# Sheet1.net
KiCad netlist of a schematic drawn in Altium Designer
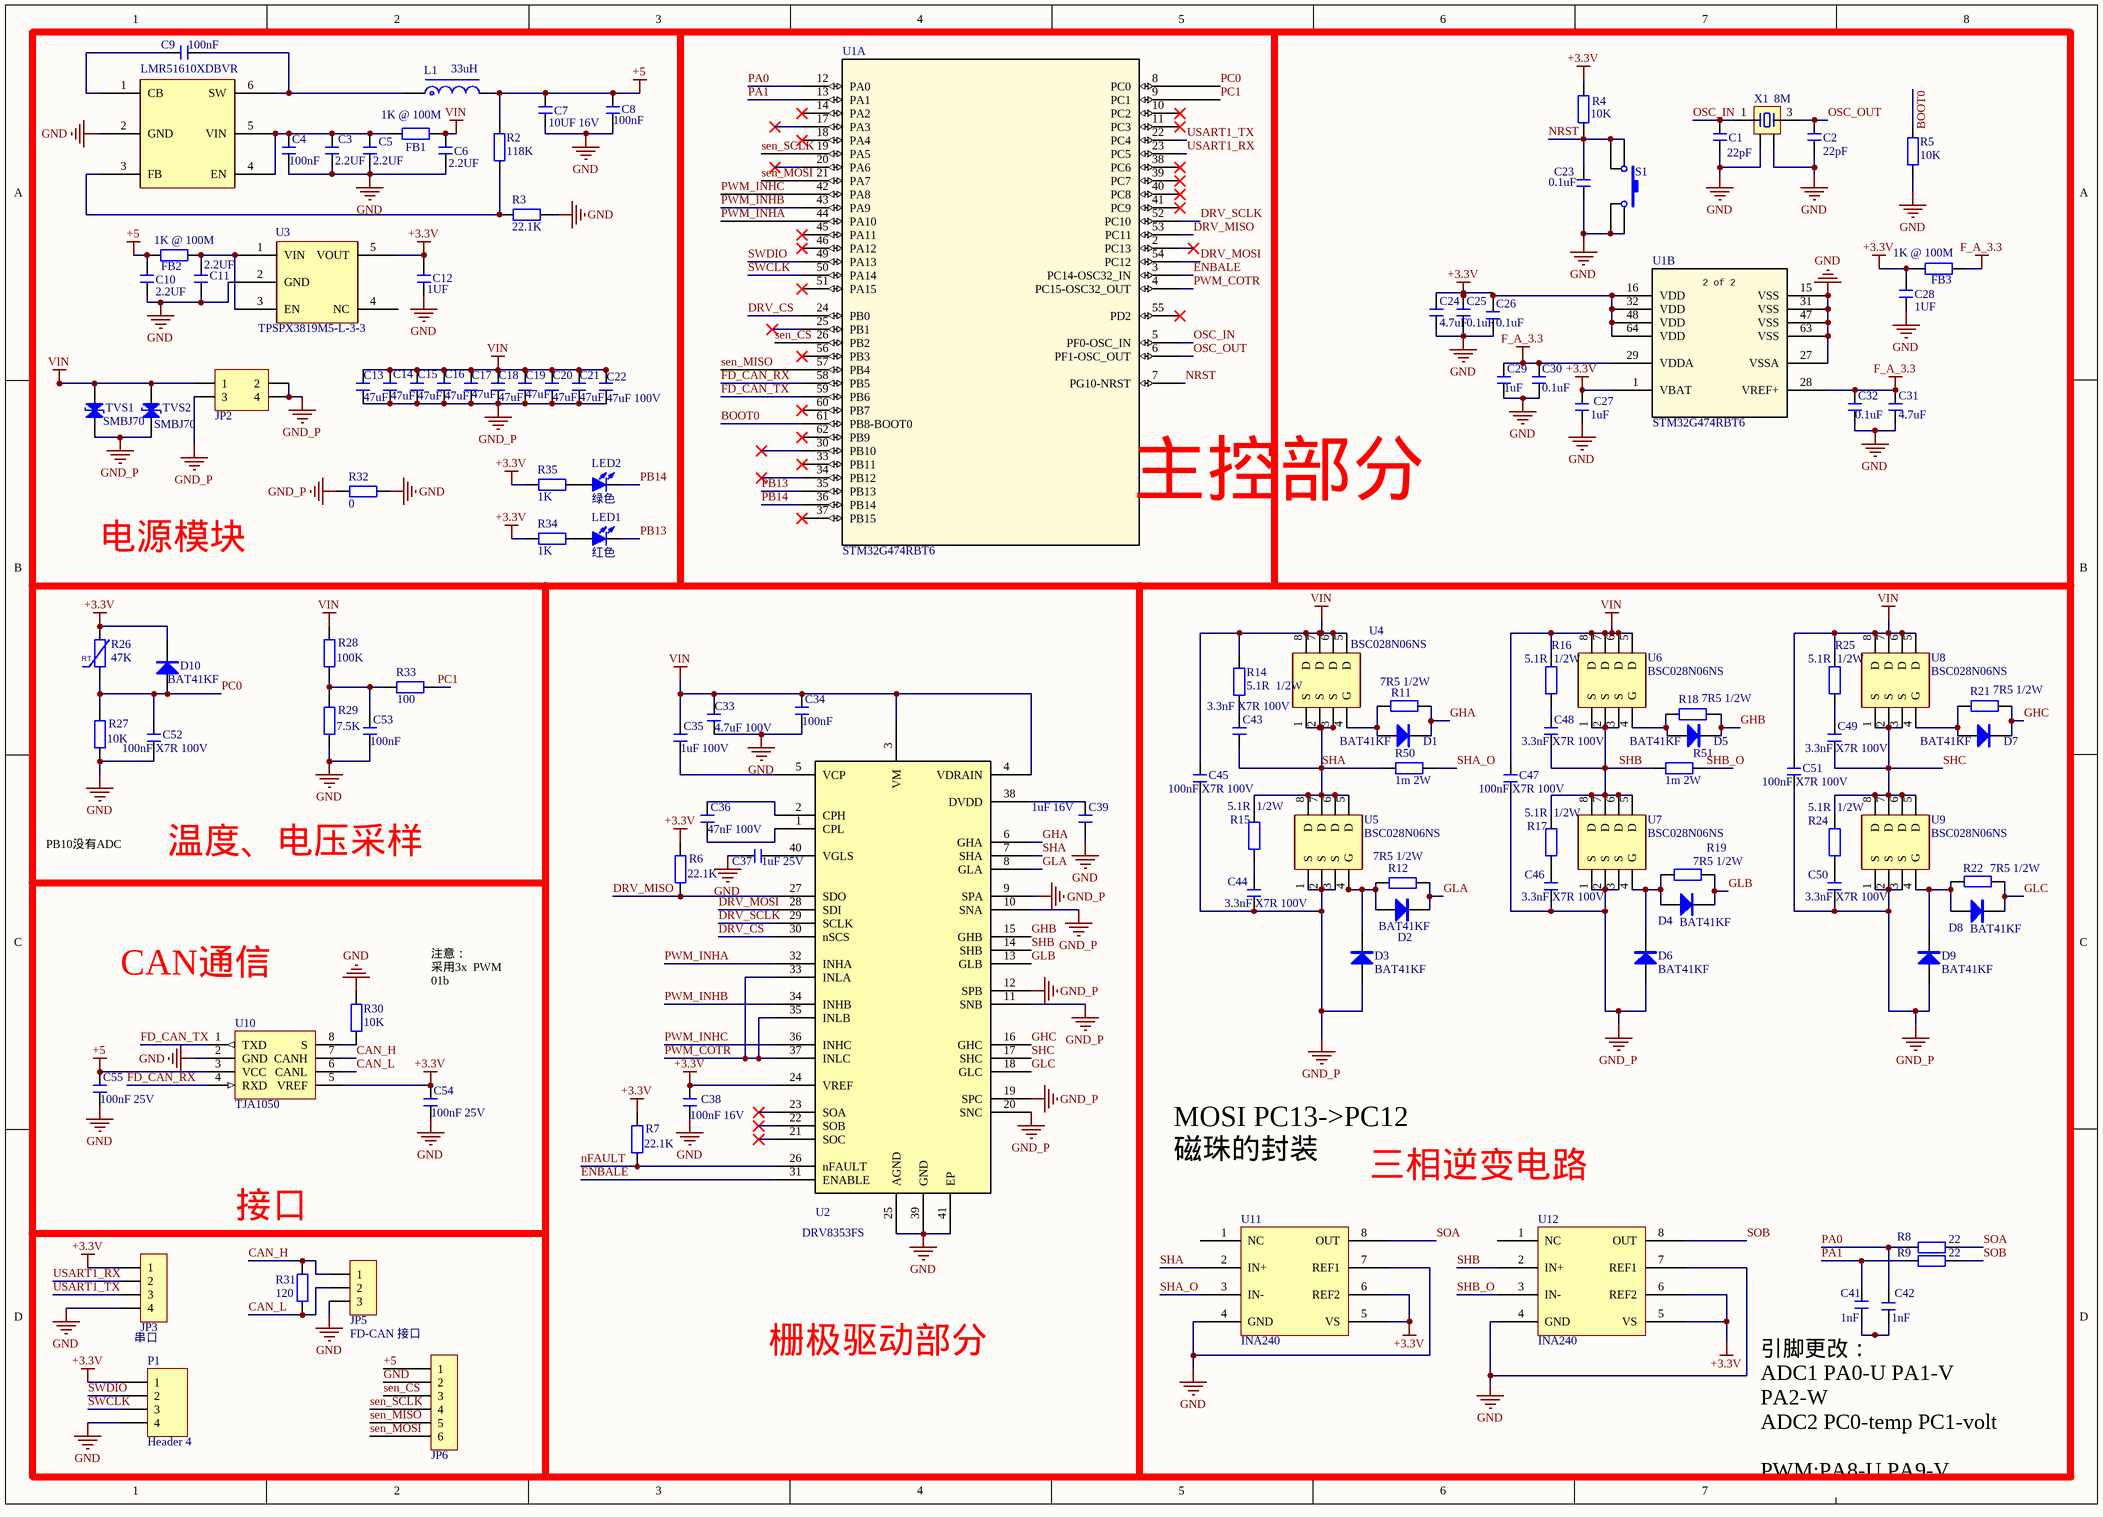
[diagram p0: Sheet1.SchDoc]

(export (version "E")
  (design (tool "Eeschema 10.0.6"))
  (components
    (comp (ref "C1")
      (value "22pF")
      (footprint "C0402_L")
      (description "贴片电容")
      (libsource (lib "0.1 - 电阻-电容-电感") (part "C"))
    )
    (comp (ref "C2")
      (value "22pF")
      (footprint "C0402_L")
      (description "贴片电容")
      (libsource (lib "0.1 - 电阻-电容-电感") (part "C"))
    )
    (comp (ref "C3")
      (value "2.2UF")
      (footprint "C0603_L")
      (description "贴片电容")
      (libsource (lib "0.1 - 电阻-电容-电感") (part "C"))
    )
    (comp (ref "C4")
      (value "100nF")
      (footprint "C0603_L")
      (description "贴片电容")
      (libsource (lib "0.1 - 电阻-电容-电感") (part "C"))
    )
    (comp (ref "C5")
      (value "2.2UF")
      (footprint "C0603_L")
      (description "贴片电容")
      (libsource (lib "0.1 - 电阻-电容-电感") (part "C"))
    )
    (comp (ref "C6")
      (value "2.2UF")
      (footprint "C0603_L")
      (description "贴片电容")
      (libsource (lib "0.1 - 电阻-电容-电感") (part "C"))
    )
    (comp (ref "C7")
      (value "10UF 16V")
      (footprint "C0402_L")
      (description "贴片电容")
      (libsource (lib "0.1 - 电阻-电容-电感") (part "C"))
    )
    (comp (ref "C8")
      (value "100nF")
      (footprint "C0402_L")
      (description "贴片电容")
      (libsource (lib "0.1 - 电阻-电容-电感") (part "C"))
    )
    (comp (ref "C9")
      (value "100nF")
      (footprint "C0603_L")
      (description "贴片电容")
      (libsource (lib "0.1 - 电阻-电容-电感") (part "C"))
    )
    (comp (ref "C10")
      (value "2.2UF")
      (footprint "C0402_L")
      (description "贴片电容")
      (libsource (lib "0.1 - 电阻-电容-电感") (part "C"))
    )
    (comp (ref "C11")
      (value "2.2UF")
      (footprint "C0402_L")
      (description "贴片电容")
      (libsource (lib "0.1 - 电阻-电容-电感") (part "C"))
    )
    (comp (ref "C12")
      (value "1UF")
      (footprint "C0402_L")
      (description "贴片电容")
      (libsource (lib "0.1 - 电阻-电容-电感") (part "C"))
    )
    (comp (ref "C13")
      (value "47uF")
      (footprint "C1206_L")
      (description "贴片电容")
      (libsource (lib "0.1 - 电阻-电容-电感") (part "C"))
    )
    (comp (ref "C14")
      (value "47uF")
      (footprint "C1206_L")
      (description "贴片电容")
      (libsource (lib "0.1 - 电阻-电容-电感") (part "C"))
    )
    (comp (ref "C15")
      (value "47uF")
      (footprint "C1206_L")
      (description "贴片电容")
      (libsource (lib "0.1 - 电阻-电容-电感") (part "C"))
    )
    (comp (ref "C16")
      (value "47uF")
      (footprint "C1206_L")
      (description "贴片电容")
      (libsource (lib "0.1 - 电阻-电容-电感") (part "C"))
    )
    (comp (ref "C17")
      (value "47uF")
      (footprint "C1206_L")
      (description "贴片电容")
      (libsource (lib "0.1 - 电阻-电容-电感") (part "C"))
    )
    (comp (ref "C18")
      (value "47uF")
      (footprint "C1206_L")
      (description "贴片电容")
      (libsource (lib "0.1 - 电阻-电容-电感") (part "C"))
    )
    (comp (ref "C19")
      (value "47uF")
      (footprint "C1206_L")
      (description "贴片电容")
      (libsource (lib "0.1 - 电阻-电容-电感") (part "C"))
    )
    (comp (ref "C20")
      (value "47uF")
      (footprint "C1206_L")
      (description "贴片电容")
      (libsource (lib "0.1 - 电阻-电容-电感") (part "C"))
    )
    (comp (ref "C21")
      (value "47uF")
      (footprint "C1206_L")
      (description "贴片电容")
      (libsource (lib "0.1 - 电阻-电容-电感") (part "C"))
    )
    (comp (ref "C22")
      (value "47uF 100V")
      (footprint "C1206_L")
      (description "贴片电容")
      (libsource (lib "0.1 - 电阻-电容-电感") (part "C"))
    )
    (comp (ref "C23")
      (value "0.1uF")
      (footprint "C0402_L")
      (description "贴片电容")
      (libsource (lib "0.1 - 电阻-电容-电感") (part "C"))
    )
    (comp (ref "C24")
      (value "4.7uF")
      (footprint "C0402_L")
      (description "贴片电容")
      (libsource (lib "0.1 - 电阻-电容-电感") (part "C"))
    )
    (comp (ref "C25")
      (value "0.1uF")
      (footprint "C0402_L")
      (description "贴片电容")
      (libsource (lib "0.1 - 电阻-电容-电感") (part "C"))
    )
    (comp (ref "C26")
      (value "0.1uF")
      (footprint "C0402_L")
      (description "贴片电容")
      (libsource (lib "0.1 - 电阻-电容-电感") (part "C"))
    )
    (comp (ref "C27")
      (value "1uF")
      (footprint "C0402_L")
      (description "贴片电容")
      (libsource (lib "0.1 - 电阻-电容-电感") (part "C"))
    )
    (comp (ref "C28")
      (value "1UF")
      (footprint "C0402_L")
      (description "贴片电容")
      (libsource (lib "0.1 - 电阻-电容-电感") (part "C"))
    )
    (comp (ref "C29")
      (value "1uF")
      (footprint "C0402_L")
      (description "贴片电容")
      (libsource (lib "0.1 - 电阻-电容-电感") (part "C"))
    )
    (comp (ref "C30")
      (value "0.1uF")
      (footprint "C0402_L")
      (description "贴片电容")
      (libsource (lib "0.1 - 电阻-电容-电感") (part "C"))
    )
    (comp (ref "C31")
      (value "4.7uF")
      (footprint "C0402_L")
      (description "贴片电容")
      (libsource (lib "0.1 - 电阻-电容-电感") (part "C"))
    )
    (comp (ref "C32")
      (value "0.1uF")
      (footprint "C0402_L")
      (description "贴片电容")
      (libsource (lib "0.1 - 电阻-电容-电感") (part "C"))
    )
    (comp (ref "C33")
      (value "4.7uF 100V")
      (footprint "C0603_L")
      (description "贴片电容")
      (libsource (lib "0.1 - 电阻-电容-电感") (part "C"))
    )
    (comp (ref "C34")
      (value "100nF")
      (footprint "C0603_L")
      (description "贴片电容")
      (libsource (lib "0.1 - 电阻-电容-电感") (part "C"))
    )
    (comp (ref "C35")
      (value "1uF 100V")
      (footprint "C0603_L")
      (description "贴片电容")
      (libsource (lib "0.1 - 电阻-电容-电感") (part "C"))
    )
    (comp (ref "C36")
      (value "47nF 100V")
      (footprint "C0603_L")
      (description "贴片电容")
      (libsource (lib "0.1 - 电阻-电容-电感") (part "C"))
    )
    (comp (ref "C37")
      (value "1uF 25V")
      (footprint "C0603_L")
      (description "贴片电容")
      (libsource (lib "0.1 - 电阻-电容-电感") (part "C"))
    )
    (comp (ref "C38")
      (value "100nF 16V")
      (footprint "C0402_L")
      (description "贴片电容")
      (libsource (lib "0.1 - 电阻-电容-电感") (part "C"))
    )
    (comp (ref "C39")
      (value "1uF 16V")
      (footprint "C0603_L")
      (description "贴片电容")
      (libsource (lib "0.1 - 电阻-电容-电感") (part "C"))
    )
    (comp (ref "C41")
      (value "1nF")
      (footprint "C0402_L")
      (description "贴片电容")
      (libsource (lib "0.1 - 电阻-电容-电感") (part "C"))
    )
    (comp (ref "C42")
      (value "1nF")
      (footprint "C0402_L")
      (description "贴片电容")
      (libsource (lib "0.1 - 电阻-电容-电感") (part "C"))
    )
    (comp (ref "C43")
      (value "3.3nF X7R 100V")
      (footprint "C1206_L")
      (description "贴片电容")
      (libsource (lib "0.1 - 电阻-电容-电感") (part "C"))
    )
    (comp (ref "C44")
      (value "3.3nF X7R 100V")
      (footprint "C1206_L")
      (description "贴片电容")
      (libsource (lib "0.1 - 电阻-电容-电感") (part "C"))
    )
    (comp (ref "C45")
      (value "100nF X7R 100V")
      (footprint "C0603_L")
      (description "贴片电容")
      (libsource (lib "0.1 - 电阻-电容-电感") (part "C"))
    )
    (comp (ref "C46")
      (value "3.3nF X7R 100V")
      (footprint "C1206_L")
      (description "贴片电容")
      (libsource (lib "0.1 - 电阻-电容-电感") (part "C"))
    )
    (comp (ref "C47")
      (value "100nF X7R 100V")
      (footprint "C0603_L")
      (description "贴片电容")
      (libsource (lib "0.1 - 电阻-电容-电感") (part "C"))
    )
    (comp (ref "C48")
      (value "3.3nF X7R 100V")
      (footprint "C1206_L")
      (description "贴片电容")
      (libsource (lib "0.1 - 电阻-电容-电感") (part "C"))
    )
    (comp (ref "C49")
      (value "3.3nF X7R 100V")
      (footprint "C1206_L")
      (description "贴片电容")
      (libsource (lib "0.1 - 电阻-电容-电感") (part "C"))
    )
    (comp (ref "C50")
      (value "3.3nF X7R 100V")
      (footprint "C1206_L")
      (description "贴片电容")
      (libsource (lib "0.1 - 电阻-电容-电感") (part "C"))
    )
    (comp (ref "C51")
      (value "100nF X7R 100V")
      (footprint "C0603_L")
      (description "贴片电容")
      (libsource (lib "0.1 - 电阻-电容-电感") (part "C"))
    )
    (comp (ref "C52")
      (value "100nF X7R 100V")
      (footprint "C0603_L")
      (description "贴片电容")
      (libsource (lib "0.1 - 电阻-电容-电感") (part "C"))
    )
    (comp (ref "C53")
      (value "100nF")
      (footprint "C0402_L")
      (description "贴片电容")
      (libsource (lib "0.1 - 电阻-电容-电感") (part "C"))
    )
    (comp (ref "C54")
      (value "100nF 25V")
      (footprint "C0402_L")
      (description "贴片电容")
      (libsource (lib "0.1 - 电阻-电容-电感") (part "C"))
    )
    (comp (ref "C55")
      (value "100nF 25V")
      (footprint "C0402_L")
      (description "贴片电容")
      (libsource (lib "0.1 - 电阻-电容-电感") (part "C"))
    )
    (comp (ref "D1")
      (value "BAT41KF")
      (footprint "SOD-523")
      (description "肖特基二极管")
      (fields (field (name "版权归属") "封装库来自淘宝 ID：黄晶宝石"))
      (libsource (lib "0.2 - 二极管-整流桥") (part "SR540"))
    )
    (comp (ref "D2")
      (value "BAT41KF")
      (footprint "SOD-523")
      (description "肖特基二极管")
      (fields (field (name "版权归属") "封装库来自淘宝 ID：黄晶宝石"))
      (libsource (lib "0.2 - 二极管-整流桥") (part "SR540"))
    )
    (comp (ref "D3")
      (value "BAT41KF")
      (footprint "SOD-523")
      (description "肖特基二极管")
      (fields (field (name "版权归属") "封装库来自淘宝 ID：黄晶宝石"))
      (libsource (lib "0.2 - 二极管-整流桥") (part "SR540"))
    )
    (comp (ref "D4")
      (value "BAT41KF")
      (footprint "SOD-523")
      (description "肖特基二极管")
      (fields (field (name "版权归属") "封装库来自淘宝 ID：黄晶宝石"))
      (libsource (lib "0.2 - 二极管-整流桥") (part "SR540"))
    )
    (comp (ref "D5")
      (value "BAT41KF")
      (footprint "SOD-523")
      (description "肖特基二极管")
      (fields (field (name "版权归属") "封装库来自淘宝 ID：黄晶宝石"))
      (libsource (lib "0.2 - 二极管-整流桥") (part "SR540"))
    )
    (comp (ref "D6")
      (value "BAT41KF")
      (footprint "SOD-523")
      (description "肖特基二极管")
      (fields (field (name "版权归属") "封装库来自淘宝 ID：黄晶宝石"))
      (libsource (lib "0.2 - 二极管-整流桥") (part "SR540"))
    )
    (comp (ref "D7")
      (value "BAT41KF")
      (footprint "SOD-523")
      (description "肖特基二极管")
      (fields (field (name "版权归属") "封装库来自淘宝 ID：黄晶宝石"))
      (libsource (lib "0.2 - 二极管-整流桥") (part "SR540"))
    )
    (comp (ref "D8")
      (value "BAT41KF")
      (footprint "SOD-523")
      (description "肖特基二极管")
      (fields (field (name "版权归属") "封装库来自淘宝 ID：黄晶宝石"))
      (libsource (lib "0.2 - 二极管-整流桥") (part "SR540"))
    )
    (comp (ref "D9")
      (value "BAT41KF")
      (footprint "SOD-523")
      (description "肖特基二极管")
      (fields (field (name "版权归属") "封装库来自淘宝 ID：黄晶宝石"))
      (libsource (lib "0.2 - 二极管-整流桥") (part "SR540"))
    )
    (comp (ref "D10")
      (value "BAT41KF")
      (footprint "SOD-523")
      (description "肖特基二极管")
      (fields (field (name "版权归属") "封装库来自淘宝 ID：黄晶宝石"))
      (libsource (lib "0.2 - 二极管-整流桥") (part "SR540"))
    )
    (comp (ref "FB1")
      (value "1K @ 100M")
      (footprint "R1206_L")
      (description "贴片电阻")
      (fields (field (name "版权归属") "来自淘宝 ID：黄晶宝石"))
      (libsource (lib "0.1 - 电阻-电容-电感") (part "R"))
    )
    (comp (ref "FB2")
      (value "1K @ 100M")
      (footprint "R1206_L")
      (description "贴片电阻")
      (fields (field (name "版权归属") "来自淘宝 ID：黄晶宝石"))
      (libsource (lib "0.1 - 电阻-电容-电感") (part "R"))
    )
    (comp (ref "FB3")
      (value "1K @ 100M")
      (footprint "R0805_L")
      (description "贴片电阻")
      (fields (field (name "版权归属") "来自淘宝 ID：黄晶宝石"))
      (libsource (lib "0.1 - 电阻-电容-电感") (part "R"))
    )
    (comp (ref "JP2")
      (value "Header2X2")
      (footprint "TX60PW-M20")
      (description "2*2P接插件")
      (libsource (lib "5.3 - 接插件-脚距2.0") (part "Header 2X2"))
    )
    (comp (ref "JP3")
      (value "串口")
      (footprint "MX 1.25-WI-4P")
      (description "4P接插件")
      (libsource (lib "5.0 - 接插件-脚距1.25") (part "Header 4"))
    )
    (comp (ref "JP5")
      (value "FD-CAN 接口")
      (footprint "XH2.54-WI-3P")
      (description "3P接插件")
      (fields (field (name "版权归属") "封装库来自淘宝 ID：黄晶宝石"))
      (libsource (lib "5.4 - 接插件-脚距2.54 (100mil) ") (part "Header 3"))
    )
    (comp (ref "JP6")
      (value "HDR-1X6")
      (footprint "MX 1.25-WI-6P")
      (description "6P接插件")
      (fields (field (name "版权归属") "封装库来自淘宝 ID：黄晶宝石"))
      (libsource (lib "5.0 - 接插件-脚距1.25") (part "Header 6"))
    )
    (comp (ref "L1")
      (value "33uH")
      (footprint "NR4030")
      (description "NR磁胶电感")
      (fields (field (name "版权归属") "来自淘宝 ID：黄晶宝石"))
      (libsource (lib "0.1 - 电阻-电容-电感") (part "L-NR"))
    )
    (comp (ref "LED1")
      (value "红色")
      (footprint "LED0603_R")
      (description "贴片LED")
      (fields (field (name "版权归属") "封装库来自淘宝 ID：黄晶宝石"))
      (libsource (lib "0.3 - LED发光二极管") (part "LED-SMD"))
    )
    (comp (ref "LED2")
      (value "绿色")
      (footprint "LED0603_R")
      (description "贴片LED")
      (fields (field (name "版权归属") "封装库来自淘宝 ID：黄晶宝石"))
      (libsource (lib "0.3 - LED发光二极管") (part "LED-SMD"))
    )
    (comp (ref "LMR51610XDBVR")
      (value "Component_1")
      (footprint "SOT23-6M")
      (libsource (lib "LMR51610XDBVR") (part "Component_1"))
    )
    (comp (ref "P1")
      (value "Header 4")
      (footprint "HDR1X4")
      (description "Header, 4-Pin")
      (fields (field (name "PUBLISHER") "Altium Limited"))
      (libsource (lib "Miscellaneous Connectors") (part "Header 4"))
    )
    (comp (ref "R2")
      (value "118K")
      (footprint "R0402_L")
      (description "贴片电阻")
      (fields (field (name "版权归属") "来自淘宝 ID：黄晶宝石"))
      (libsource (lib "0.1 - 电阻-电容-电感") (part "R"))
    )
    (comp (ref "R3")
      (value "22.1K")
      (footprint "R0402_L")
      (description "贴片电阻")
      (fields (field (name "版权归属") "来自淘宝 ID：黄晶宝石"))
      (libsource (lib "0.1 - 电阻-电容-电感") (part "R"))
    )
    (comp (ref "R4")
      (value "10K")
      (footprint "R0402_L")
      (description "贴片电阻")
      (fields (field (name "版权归属") "来自淘宝 ID：黄晶宝石"))
      (libsource (lib "0.1 - 电阻-电容-电感") (part "R"))
    )
    (comp (ref "R5")
      (value "10K")
      (footprint "R0402_L")
      (description "贴片电阻")
      (fields (field (name "版权归属") "来自淘宝 ID：黄晶宝石"))
      (libsource (lib "0.1 - 电阻-电容-电感") (part "R"))
    )
    (comp (ref "R6")
      (value "22.1K")
      (footprint "R0402_L")
      (description "贴片电阻")
      (fields (field (name "版权归属") "来自淘宝 ID：黄晶宝石"))
      (libsource (lib "0.1 - 电阻-电容-电感") (part "R"))
    )
    (comp (ref "R7")
      (value "22.1K")
      (footprint "R0402_L")
      (description "贴片电阻")
      (fields (field (name "版权归属") "来自淘宝 ID：黄晶宝石"))
      (libsource (lib "0.1 - 电阻-电容-电感") (part "R"))
    )
    (comp (ref "R8")
      (value "22")
      (footprint "R0402_L")
      (description "贴片电阻")
      (fields (field (name "版权归属") "来自淘宝 ID：黄晶宝石"))
      (libsource (lib "0.1 - 电阻-电容-电感") (part "R"))
    )
    (comp (ref "R9")
      (value "22")
      (footprint "R0402_L")
      (description "贴片电阻")
      (fields (field (name "版权归属") "来自淘宝 ID：黄晶宝石"))
      (libsource (lib "0.1 - 电阻-电容-电感") (part "R"))
    )
    (comp (ref "R11")
      (value "7R5 1/2W")
      (footprint "R1210_M")
      (description "贴片电阻")
      (fields (field (name "版权归属") "来自淘宝 ID：黄晶宝石"))
      (libsource (lib "0.1 - 电阻-电容-电感") (part "R"))
    )
    (comp (ref "R12")
      (value "7R5 1/2W")
      (footprint "R1210_M")
      (description "贴片电阻")
      (fields (field (name "版权归属") "来自淘宝 ID：黄晶宝石"))
      (libsource (lib "0.1 - 电阻-电容-电感") (part "R"))
    )
    (comp (ref "R14")
      (value "5.1R  1/2W")
      (footprint "R1210_L")
      (description "贴片电阻")
      (fields (field (name "版权归属") "来自淘宝 ID：黄晶宝石"))
      (libsource (lib "0.1 - 电阻-电容-电感") (part "R"))
    )
    (comp (ref "R15")
      (value "5.1R  1/2W")
      (footprint "R1210_L")
      (description "贴片电阻")
      (fields (field (name "版权归属") "来自淘宝 ID：黄晶宝石"))
      (libsource (lib "0.1 - 电阻-电容-电感") (part "R"))
    )
    (comp (ref "R16")
      (value "5.1R  1/2W")
      (footprint "R1210_L")
      (description "贴片电阻")
      (fields (field (name "版权归属") "来自淘宝 ID：黄晶宝石"))
      (libsource (lib "0.1 - 电阻-电容-电感") (part "R"))
    )
    (comp (ref "R17")
      (value "5.1R  1/2W")
      (footprint "R1210_L")
      (description "贴片电阻")
      (fields (field (name "版权归属") "来自淘宝 ID：黄晶宝石"))
      (libsource (lib "0.1 - 电阻-电容-电感") (part "R"))
    )
    (comp (ref "R18")
      (value "7R5 1/2W")
      (footprint "R1210_M")
      (description "贴片电阻")
      (fields (field (name "版权归属") "来自淘宝 ID：黄晶宝石"))
      (libsource (lib "0.1 - 电阻-电容-电感") (part "R"))
    )
    (comp (ref "R19")
      (value "7R5 1/2W")
      (footprint "R1210_M")
      (description "贴片电阻")
      (fields (field (name "版权归属") "来自淘宝 ID：黄晶宝石"))
      (libsource (lib "0.1 - 电阻-电容-电感") (part "R"))
    )
    (comp (ref "R21")
      (value "7R5 1/2W")
      (footprint "R1210_M")
      (description "贴片电阻")
      (fields (field (name "版权归属") "来自淘宝 ID：黄晶宝石"))
      (libsource (lib "0.1 - 电阻-电容-电感") (part "R"))
    )
    (comp (ref "R22")
      (value "7R5 1/2W")
      (footprint "R1210_M")
      (description "贴片电阻")
      (fields (field (name "版权归属") "来自淘宝 ID：黄晶宝石"))
      (libsource (lib "0.1 - 电阻-电容-电感") (part "R"))
    )
    (comp (ref "R24")
      (value "5.1R  1/2W")
      (footprint "R1210_L")
      (description "贴片电阻")
      (fields (field (name "版权归属") "来自淘宝 ID：黄晶宝石"))
      (libsource (lib "0.1 - 电阻-电容-电感") (part "R"))
    )
    (comp (ref "R25")
      (value "5.1R  1/2W")
      (footprint "R1210_L")
      (description "贴片电阻")
      (fields (field (name "版权归属") "来自淘宝 ID：黄晶宝石"))
      (libsource (lib "0.1 - 电阻-电容-电感") (part "R"))
    )
    (comp (ref "R26")
      (value "47K")
      (footprint "R0402-HP_L")
      (description "热敏电阻")
      (fields (field (name "版权归属") "封装库来自淘宝 ID：黄晶宝石"))
      (libsource (lib "0.1 - 电阻-电容-电感") (part "RT"))
    )
    (comp (ref "R27")
      (value "10K")
      (footprint "R0402_L")
      (description "贴片电阻")
      (fields (field (name "版权归属") "来自淘宝 ID：黄晶宝石"))
      (libsource (lib "0.1 - 电阻-电容-电感") (part "R"))
    )
    (comp (ref "R28")
      (value "100K")
      (footprint "R0402_L")
      (description "贴片电阻")
      (fields (field (name "版权归属") "来自淘宝 ID：黄晶宝石"))
      (libsource (lib "0.1 - 电阻-电容-电感") (part "R"))
    )
    (comp (ref "R29")
      (value "7.5K")
      (footprint "R0402_L")
      (description "贴片电阻")
      (fields (field (name "版权归属") "来自淘宝 ID：黄晶宝石"))
      (libsource (lib "0.1 - 电阻-电容-电感") (part "R"))
    )
    (comp (ref "R30")
      (value "10K")
      (footprint "R0402_L")
      (description "贴片电阻")
      (fields (field (name "版权归属") "来自淘宝 ID：黄晶宝石"))
      (libsource (lib "0.1 - 电阻-电容-电感") (part "R"))
    )
    (comp (ref "R31")
      (value "120")
      (footprint "R0402_L")
      (description "贴片电阻")
      (fields (field (name "版权归属") "来自淘宝 ID：黄晶宝石"))
      (libsource (lib "0.1 - 电阻-电容-电感") (part "R"))
    )
    (comp (ref "R32")
      (value "0")
      (footprint "R1206_L")
      (description "贴片电阻")
      (fields (field (name "版权归属") "来自淘宝 ID：黄晶宝石"))
      (libsource (lib "0.1 - 电阻-电容-电感") (part "R"))
    )
    (comp (ref "R33")
      (value "100")
      (footprint "R0402_L")
      (description "贴片电阻")
      (fields (field (name "版权归属") "来自淘宝 ID：黄晶宝石"))
      (libsource (lib "0.1 - 电阻-电容-电感") (part "R"))
    )
    (comp (ref "R34")
      (value "1K")
      (footprint "R0402_L")
      (description "贴片电阻")
      (fields (field (name "版权归属") "来自淘宝 ID：黄晶宝石"))
      (libsource (lib "0.1 - 电阻-电容-电感") (part "R"))
    )
    (comp (ref "R35")
      (value "1K")
      (footprint "R0402_L")
      (description "贴片电阻")
      (fields (field (name "版权归属") "来自淘宝 ID：黄晶宝石"))
      (libsource (lib "0.1 - 电阻-电容-电感") (part "R"))
    )
    (comp (ref "R50")
      (value "1m 2W")
      (footprint "R2512_M")
      (description "贴片电阻")
      (fields (field (name "版权归属") "来自淘宝 ID：黄晶宝石"))
      (libsource (lib "0.1 - 电阻-电容-电感") (part "R"))
    )
    (comp (ref "R51")
      (value "1m 2W")
      (footprint "R2512_M")
      (description "贴片电阻")
      (fields (field (name "版权归属") "来自淘宝 ID：黄晶宝石"))
      (libsource (lib "0.1 - 电阻-电容-电感") (part "R"))
    )
    (comp (ref "S1")
      (value "SW-PB4")
      (footprint "SW SMD-4*4*1.5")
      (description "微动开关")
      (fields (field (name "PUBLISHER") "Altium Limited"))
      (libsource (lib "0.7 - 常用按键-开关") (part "SW-PB4"))
    )
    (comp (ref "TVS1")
      (value "SMBJ70")
      (footprint "SMB")
      (description "瞬态电压抑制二极管")
      (fields (field (name "版权归属") "封装库来自淘宝 ID：黄晶宝石"))
      (libsource (lib "0.2 - 二极管-整流桥") (part "DR"))
    )
    (comp (ref "TVS2")
      (value "SMBJ70")
      (footprint "SMB")
      (description "瞬态电压抑制二极管")
      (fields (field (name "版权归属") "封装库来自淘宝 ID：黄晶宝石"))
      (libsource (lib "0.2 - 二极管-整流桥") (part "DR"))
    )
    (comp (ref "U1")
      (value "STM32G474RBT6")
      (footprint "FOC_LQFP64-10x10mm")
      (description "No Description Available")
      (fields (field (name "COPYRIGHT") "Copyright (C) 2018 Accelerated Designs. All rights reserved"))
      (libsource (lib "STM32G") (part "STM32G474RBT6"))
    )
    (comp (ref "U2")
      (value "DRV8353FS")
      (footprint "QFN40 6X6_M")
      (libsource (lib "My_FOC") (part "DRV8353RS"))
    )
    (comp (ref "U3")
      (value "TPSPX3819M5-L-3-3")
      (footprint "SOT23-5")
      (libsource (lib "My_FOC") (part "TPSPX3819M5-L-3-3"))
    )
    (comp (ref "U4")
      (value "BSC028N06NS")
      (footprint "PG-TDSON-8_L5.0-W6.0-P1.27-LS6.2-BL-EP")
      (libsource (lib "My_FOC") (part "BSC028N06NS"))
    )
    (comp (ref "U5")
      (value "BSC028N06NS")
      (footprint "PG-TDSON-8_L5.0-W6.0-P1.27-LS6.2-BL-EP")
      (libsource (lib "My_FOC") (part "BSC028N06NS"))
    )
    (comp (ref "U6")
      (value "BSC028N06NS")
      (footprint "PG-TDSON-8_L5.0-W6.0-P1.27-LS6.2-BL-EP")
      (libsource (lib "My_FOC") (part "BSC028N06NS"))
    )
    (comp (ref "U7")
      (value "BSC028N06NS")
      (footprint "PG-TDSON-8_L5.0-W6.0-P1.27-LS6.2-BL-EP")
      (libsource (lib "My_FOC") (part "BSC028N06NS"))
    )
    (comp (ref "U8")
      (value "BSC028N06NS")
      (footprint "PG-TDSON-8_L5.0-W6.0-P1.27-LS6.2-BL-EP")
      (libsource (lib "My_FOC") (part "BSC028N06NS"))
    )
    (comp (ref "U9")
      (value "BSC028N06NS")
      (footprint "PG-TDSON-8_L5.0-W6.0-P1.27-LS6.2-BL-EP")
      (libsource (lib "My_FOC") (part "BSC028N06NS"))
    )
    (comp (ref "U10")
      (value "TJA1050")
      (footprint "VSON-8")
      (description "CAN总线收发芯片")
      (fields (field (name "版权归属") "封装库来自淘宝 ID：黄晶宝石"))
      (libsource (lib "1.0 - 常见芯片") (part "TJA1050"))
    )
    (comp (ref "U11") (value "INA240") (footprint "TSSOP8") (libsource (lib "FOC_V1") (part "INA240")))
    (comp (ref "U12") (value "INA240") (footprint "TSSOP8") (libsource (lib "FOC_V1") (part "INA240")))
    (comp (ref "X1")
      (value "8M")
      (footprint "OSC 3225-4P")
      (description "4脚无源晶振")
      (fields (field (name "版权归属") "封装库来自淘宝卖家 ID：黄晶宝石"))
      (libsource (lib "2.0 - 保险丝-晶振-光耦") (part "XTAL-4P"))
    )
  )
  (nets
    (net (code "1") (name "+3.3V") (class "Default")
      (node (ref "C12") (pin "2") (pinfunction "2_2") (pintype "passive"))
      (node (ref "C24") (pin "2") (pinfunction "2_2") (pintype "passive"))
      (node (ref "C25") (pin "2") (pinfunction "2_2") (pintype "passive"))
      (node (ref "C26") (pin "2") (pinfunction "2_2") (pintype "passive"))
      (node (ref "C27") (pin "2") (pinfunction "2_2") (pintype "passive"))
      (node (ref "C28") (pin "2") (pinfunction "2_2") (pintype "passive"))
      (node (ref "C38") (pin "2") (pinfunction "2_2") (pintype "passive"))
      (node (ref "C54") (pin "2") (pinfunction "2_2") (pintype "passive"))
      (node (ref "D10") (pin "2") (pinfunction "K_2") (pintype "passive"))
      (node (ref "FB3") (pin "1") (pinfunction "1_1") (pintype "passive"))
      (node (ref "JP3") (pin "1") (pinfunction "1_1") (pintype "passive"))
      (node (ref "P1") (pin "1") (pinfunction "1_1") (pintype "passive"))
      (node (ref "R26") (pin "2") (pinfunction "2_2") (pintype "passive"))
      (node (ref "R34") (pin "2") (pinfunction "2_2") (pintype "passive"))
      (node (ref "R35") (pin "2") (pinfunction "2_2") (pintype "passive"))
      (node (ref "R4") (pin "2") (pinfunction "2_2") (pintype "passive"))
      (node (ref "R6") (pin "2") (pinfunction "2_2") (pintype "passive"))
      (node (ref "R7") (pin "2") (pinfunction "2_2") (pintype "passive"))
      (node (ref "U1") (pin "1") (pinfunction "VBAT_1") (pintype "power_in"))
      (node (ref "U1") (pin "16") (pinfunction "VDD_16") (pintype "power_in"))
      (node (ref "U1") (pin "32") (pinfunction "VDD_32") (pintype "power_in"))
      (node (ref "U1") (pin "48") (pinfunction "VDD_48") (pintype "power_in"))
      (node (ref "U1") (pin "64") (pinfunction "VDD_64") (pintype "power_in"))
      (node (ref "U10") (pin "5") (pinfunction "VREF_5") (pintype "passive"))
      (node (ref "U11") (pin "5") (pinfunction "VS_5") (pintype "passive"))
      (node (ref "U11") (pin "6") (pinfunction "REF2_6") (pintype "passive"))
      (node (ref "U12") (pin "5") (pinfunction "VS_5") (pintype "passive"))
      (node (ref "U12") (pin "6") (pinfunction "REF2_6") (pintype "passive"))
      (node (ref "U2") (pin "24") (pinfunction "VREF_24") (pintype "passive"))
      (node (ref "U3") (pin "5") (pinfunction "VOUT_5") (pintype "passive"))
    )
    (net (code "2") (name "+5") (class "Default")
      (node (ref "C10") (pin "2") (pinfunction "2_2") (pintype "passive"))
      (node (ref "C55") (pin "2") (pinfunction "2_2") (pintype "passive"))
      (node (ref "C7") (pin "2") (pinfunction "2_2") (pintype "passive"))
      (node (ref "C8") (pin "2") (pinfunction "2_2") (pintype "passive"))
      (node (ref "FB2") (pin "1") (pinfunction "1_1") (pintype "passive"))
      (node (ref "JP6") (pin "1") (pinfunction "1_1") (pintype "passive"))
      (node (ref "L1") (pin "2") (pinfunction "2_2") (pintype "passive"))
      (node (ref "R2") (pin "2") (pinfunction "2_2") (pintype "passive"))
      (node (ref "U10") (pin "3") (pinfunction "VCC_3") (pintype "passive"))
    )
    (net (code "3") (name "/BOOT0") (class "Default")
      (node (ref "R5") (pin "2") (pinfunction "2_2") (pintype "passive"))
      (node (ref "U1") (pin "61") (pinfunction "PB8-BOOT0_61") (pintype "bidirectional"))
    )
    (net (code "4") (name "/CAN_H") (class "Default")
      (node (ref "JP5") (pin "1") (pinfunction "1_1") (pintype "passive"))
      (node (ref "R31") (pin "1") (pinfunction "1_1") (pintype "passive"))
      (node (ref "U10") (pin "7") (pinfunction "CANH_7") (pintype "passive"))
    )
    (net (code "5") (name "/CAN_L") (class "Default")
      (node (ref "JP5") (pin "2") (pinfunction "2_2") (pintype "passive"))
      (node (ref "R31") (pin "2") (pinfunction "2_2") (pintype "passive"))
      (node (ref "U10") (pin "6") (pinfunction "CANL_6") (pintype "passive"))
    )
    (net (code "6") (name "/DRV_CS") (class "Default")
      (node (ref "U1") (pin "24") (pinfunction "PB0_24") (pintype "bidirectional"))
      (node (ref "U2") (pin "30") (pinfunction "nSCS_30") (pintype "passive"))
    )
    (net (code "7") (name "/DRV_MISO") (class "Default")
      (node (ref "R6") (pin "1") (pinfunction "1_1") (pintype "passive"))
      (node (ref "U1") (pin "53") (pinfunction "PC11_53") (pintype "bidirectional"))
      (node (ref "U2") (pin "27") (pinfunction "SDO_27") (pintype "passive"))
    )
    (net (code "8") (name "/DRV_MOSI") (class "Default")
      (node (ref "U1") (pin "54") (pinfunction "PC12_54") (pintype "bidirectional"))
      (node (ref "U2") (pin "28") (pinfunction "SDI_28") (pintype "passive"))
    )
    (net (code "9") (name "/DRV_SCLK") (class "Default")
      (node (ref "U1") (pin "52") (pinfunction "PC10_52") (pintype "bidirectional"))
      (node (ref "U2") (pin "29") (pinfunction "SCLK_29") (pintype "passive"))
    )
    (net (code "10") (name "/ENBALE") (class "Default")
      (node (ref "U1") (pin "3") (pinfunction "PC14-OSC32_IN_3") (pintype "bidirectional"))
      (node (ref "U2") (pin "31") (pinfunction "ENABLE_31") (pintype "passive"))
    )
    (net (code "11") (name "/FD_CAN_RX") (class "Default")
      (node (ref "U1") (pin "58") (pinfunction "PB5_58") (pintype "bidirectional"))
      (node (ref "U10") (pin "4") (pinfunction "RXD_4") (pintype "input"))
    )
    (net (code "12") (name "/FD_CAN_TX") (class "Default")
      (node (ref "U1") (pin "59") (pinfunction "PB6_59") (pintype "bidirectional"))
      (node (ref "U10") (pin "1") (pinfunction "TXD_1") (pintype "output"))
    )
    (net (code "13") (name "/GHA") (class "Default")
      (node (ref "D1") (pin "2") (pinfunction "K_2") (pintype "passive"))
      (node (ref "R11") (pin "2") (pinfunction "2_2") (pintype "passive"))
      (node (ref "U2") (pin "6") (pinfunction "GHA_6") (pintype "passive"))
    )
    (net (code "14") (name "/GHB") (class "Default")
      (node (ref "D5") (pin "2") (pinfunction "K_2") (pintype "passive"))
      (node (ref "R18") (pin "2") (pinfunction "2_2") (pintype "passive"))
      (node (ref "U2") (pin "15") (pinfunction "GHB_15") (pintype "passive"))
    )
    (net (code "15") (name "/GHC") (class "Default")
      (node (ref "D7") (pin "2") (pinfunction "K_2") (pintype "passive"))
      (node (ref "R21") (pin "2") (pinfunction "2_2") (pintype "passive"))
      (node (ref "U2") (pin "16") (pinfunction "GHC_16") (pintype "passive"))
    )
    (net (code "16") (name "/GLA") (class "Default")
      (node (ref "D2") (pin "2") (pinfunction "K_2") (pintype "passive"))
      (node (ref "R12") (pin "2") (pinfunction "2_2") (pintype "passive"))
      (node (ref "U2") (pin "8") (pinfunction "GLA_8") (pintype "passive"))
    )
    (net (code "17") (name "/GLB") (class "Default")
      (node (ref "D4") (pin "2") (pinfunction "K_2") (pintype "passive"))
      (node (ref "R19") (pin "2") (pinfunction "2_2") (pintype "passive"))
      (node (ref "U2") (pin "13") (pinfunction "GLB_13") (pintype "passive"))
    )
    (net (code "18") (name "/GLC") (class "Default")
      (node (ref "D8") (pin "2") (pinfunction "K_2") (pintype "passive"))
      (node (ref "R22") (pin "2") (pinfunction "2_2") (pintype "passive"))
      (node (ref "U2") (pin "18") (pinfunction "GLC_18") (pintype "passive"))
    )
    (net (code "19") (name "/NRST") (class "Default")
      (node (ref "C23") (pin "2") (pinfunction "2_2") (pintype "passive"))
      (node (ref "R4") (pin "1") (pinfunction "1_1") (pintype "passive"))
      (node (ref "S1") (pin "1") (pinfunction "1_1") (pintype "passive"))
      (node (ref "S1") (pin "4") (pinfunction "4_4") (pintype "passive"))
      (node (ref "U1") (pin "7") (pinfunction "PG10-NRST_7") (pintype "bidirectional"))
    )
    (net (code "20") (name "/OSC_IN") (class "Default")
      (node (ref "C1") (pin "2") (pinfunction "2_2") (pintype "passive"))
      (node (ref "U1") (pin "5") (pinfunction "PF0-OSC_IN_5") (pintype "bidirectional"))
      (node (ref "X1") (pin "1") (pinfunction "1_1") (pintype "passive"))
    )
    (net (code "21") (name "/OSC_OUT") (class "Default")
      (node (ref "C2") (pin "2") (pinfunction "2_2") (pintype "passive"))
      (node (ref "U1") (pin "6") (pinfunction "PF1-OSC_OUT_6") (pintype "bidirectional"))
      (node (ref "X1") (pin "3") (pinfunction "3_3") (pintype "passive"))
    )
    (net (code "22") (name "/PA0") (class "Default")
      (node (ref "C42") (pin "2") (pinfunction "2_2") (pintype "passive"))
      (node (ref "R8") (pin "2") (pinfunction "2_2") (pintype "passive"))
      (node (ref "U1") (pin "12") (pinfunction "PA0_12") (pintype "bidirectional"))
    )
    (net (code "23") (name "/PA1") (class "Default")
      (node (ref "C41") (pin "2") (pinfunction "2_2") (pintype "passive"))
      (node (ref "R9") (pin "2") (pinfunction "2_2") (pintype "passive"))
      (node (ref "U1") (pin "13") (pinfunction "PA1_13") (pintype "bidirectional"))
    )
    (net (code "24") (name "/PB13") (class "Default")
      (node (ref "LED1") (pin "2") (pinfunction "K_2") (pintype "passive"))
      (node (ref "U1") (pin "35") (pinfunction "PB13_35") (pintype "bidirectional"))
    )
    (net (code "25") (name "/PB14") (class "Default")
      (node (ref "LED2") (pin "2") (pinfunction "K_2") (pintype "passive"))
      (node (ref "U1") (pin "36") (pinfunction "PB14_36") (pintype "bidirectional"))
    )
    (net (code "26") (name "/PC0") (class "Default")
      (node (ref "C52") (pin "2") (pinfunction "2_2") (pintype "passive"))
      (node (ref "D10") (pin "1") (pinfunction "A_1") (pintype "passive"))
      (node (ref "R26") (pin "1") (pinfunction "1_1") (pintype "passive"))
      (node (ref "R27") (pin "2") (pinfunction "2_2") (pintype "passive"))
      (node (ref "U1") (pin "8") (pinfunction "PC0_8") (pintype "bidirectional"))
    )
    (net (code "27") (name "/PC1") (class "Default")
      (node (ref "R33") (pin "1") (pinfunction "1_1") (pintype "passive"))
      (node (ref "U1") (pin "9") (pinfunction "PC1_9") (pintype "bidirectional"))
    )
    (net (code "28") (name "/PWM_COTR") (class "Default")
      (node (ref "U1") (pin "4") (pinfunction "PC15-OSC32_OUT_4") (pintype "bidirectional"))
      (node (ref "U2") (pin "33") (pinfunction "INLA_33") (pintype "passive"))
      (node (ref "U2") (pin "35") (pinfunction "INLB_35") (pintype "passive"))
      (node (ref "U2") (pin "37") (pinfunction "INLC_37") (pintype "passive"))
    )
    (net (code "29") (name "/PWM_INHA") (class "Default")
      (node (ref "U1") (pin "44") (pinfunction "PA10_44") (pintype "bidirectional"))
      (node (ref "U2") (pin "32") (pinfunction "INHA_32") (pintype "passive"))
    )
    (net (code "30") (name "/PWM_INHB") (class "Default")
      (node (ref "U1") (pin "43") (pinfunction "PA9_43") (pintype "bidirectional"))
      (node (ref "U2") (pin "34") (pinfunction "INHB_34") (pintype "passive"))
    )
    (net (code "31") (name "/PWM_INHC") (class "Default")
      (node (ref "U1") (pin "42") (pinfunction "PA8_42") (pintype "bidirectional"))
      (node (ref "U2") (pin "36") (pinfunction "INHC_36") (pintype "passive"))
    )
    (net (code "32") (name "/SHA") (class "Default")
      (node (ref "C43") (pin "1") (pinfunction "1_1") (pintype "passive"))
      (node (ref "R15") (pin "2") (pinfunction "2_2") (pintype "passive"))
      (node (ref "R50") (pin "2") (pinfunction "2_2") (pintype "passive"))
      (node (ref "U11") (pin "2") (pinfunction "IN+_2") (pintype "passive"))
      (node (ref "U2") (pin "7") (pinfunction "SHA_7") (pintype "passive"))
      (node (ref "U4") (pin "1") (pinfunction "S_1") (pintype "passive"))
      (node (ref "U4") (pin "2") (pinfunction "S_2") (pintype "passive"))
      (node (ref "U4") (pin "3") (pinfunction "S_3") (pintype "passive"))
      (node (ref "U5") (pin "5") (pinfunction "D_5") (pintype "passive"))
      (node (ref "U5") (pin "6") (pinfunction "D_6") (pintype "passive"))
      (node (ref "U5") (pin "7") (pinfunction "D_7") (pintype "passive"))
      (node (ref "U5") (pin "8") (pinfunction "D_8") (pintype "passive"))
    )
    (net (code "33") (name "/SHA_O") (class "Default")
      (node (ref "R50") (pin "1") (pinfunction "1_1") (pintype "passive"))
      (node (ref "U11") (pin "3") (pinfunction "IN-_3") (pintype "passive"))
    )
    (net (code "34") (name "/SHB") (class "Default")
      (node (ref "C48") (pin "1") (pinfunction "1_1") (pintype "passive"))
      (node (ref "R17") (pin "2") (pinfunction "2_2") (pintype "passive"))
      (node (ref "R51") (pin "2") (pinfunction "2_2") (pintype "passive"))
      (node (ref "U12") (pin "2") (pinfunction "IN+_2") (pintype "passive"))
      (node (ref "U2") (pin "14") (pinfunction "SHB_14") (pintype "passive"))
      (node (ref "U6") (pin "1") (pinfunction "S_1") (pintype "passive"))
      (node (ref "U6") (pin "2") (pinfunction "S_2") (pintype "passive"))
      (node (ref "U6") (pin "3") (pinfunction "S_3") (pintype "passive"))
      (node (ref "U7") (pin "5") (pinfunction "D_5") (pintype "passive"))
      (node (ref "U7") (pin "6") (pinfunction "D_6") (pintype "passive"))
      (node (ref "U7") (pin "7") (pinfunction "D_7") (pintype "passive"))
      (node (ref "U7") (pin "8") (pinfunction "D_8") (pintype "passive"))
    )
    (net (code "35") (name "/SHB_O") (class "Default")
      (node (ref "R51") (pin "1") (pinfunction "1_1") (pintype "passive"))
      (node (ref "U12") (pin "3") (pinfunction "IN-_3") (pintype "passive"))
    )
    (net (code "36") (name "/SHC") (class "Default")
      (node (ref "C49") (pin "1") (pinfunction "1_1") (pintype "passive"))
      (node (ref "R24") (pin "2") (pinfunction "2_2") (pintype "passive"))
      (node (ref "U2") (pin "17") (pinfunction "SHC_17") (pintype "passive"))
      (node (ref "U8") (pin "1") (pinfunction "S_1") (pintype "passive"))
      (node (ref "U8") (pin "2") (pinfunction "S_2") (pintype "passive"))
      (node (ref "U8") (pin "3") (pinfunction "S_3") (pintype "passive"))
      (node (ref "U9") (pin "5") (pinfunction "D_5") (pintype "passive"))
      (node (ref "U9") (pin "6") (pinfunction "D_6") (pintype "passive"))
      (node (ref "U9") (pin "7") (pinfunction "D_7") (pintype "passive"))
      (node (ref "U9") (pin "8") (pinfunction "D_8") (pintype "passive"))
    )
    (net (code "37") (name "/SOA") (class "Default")
      (node (ref "R8") (pin "1") (pinfunction "1_1") (pintype "passive"))
      (node (ref "U11") (pin "8") (pinfunction "OUT_8") (pintype "passive"))
    )
    (net (code "38") (name "/SOB") (class "Default")
      (node (ref "R9") (pin "1") (pinfunction "1_1") (pintype "passive"))
      (node (ref "U12") (pin "8") (pinfunction "OUT_8") (pintype "passive"))
    )
    (net (code "39") (name "/SWCLK") (class "Default")
      (node (ref "P1") (pin "3") (pinfunction "3_3") (pintype "passive"))
      (node (ref "U1") (pin "50") (pinfunction "PA14_50") (pintype "bidirectional"))
    )
    (net (code "40") (name "/SWDIO") (class "Default")
      (node (ref "P1") (pin "2") (pinfunction "2_2") (pintype "passive"))
      (node (ref "U1") (pin "49") (pinfunction "PA13_49") (pintype "bidirectional"))
    )
    (net (code "41") (name "/USART1_RX") (class "Default")
      (node (ref "JP3") (pin "2") (pinfunction "2_2") (pintype "passive"))
      (node (ref "U1") (pin "23") (pinfunction "PC5_23") (pintype "bidirectional"))
    )
    (net (code "42") (name "/USART1_TX") (class "Default")
      (node (ref "JP3") (pin "3") (pinfunction "3_3") (pintype "passive"))
      (node (ref "U1") (pin "22") (pinfunction "PC4_22") (pintype "bidirectional"))
    )
    (net (code "43") (name "/nFAULT") (class "Default")
      (node (ref "R7") (pin "1") (pinfunction "1_1") (pintype "passive"))
      (node (ref "U2") (pin "26") (pinfunction "nFAULT_26") (pintype "passive"))
    )
    (net (code "44") (name "/sen_CS") (class "Default")
      (node (ref "JP6") (pin "3") (pinfunction "3_3") (pintype "passive"))
      (node (ref "U1") (pin "26") (pinfunction "PB2_26") (pintype "bidirectional"))
    )
    (net (code "45") (name "/sen_MISO") (class "Default")
      (node (ref "JP6") (pin "5") (pinfunction "5_5") (pintype "passive"))
      (node (ref "U1") (pin "57") (pinfunction "PB4_57") (pintype "bidirectional"))
    )
    (net (code "46") (name "/sen_MOSI") (class "Default")
      (node (ref "JP6") (pin "6") (pinfunction "6_6") (pintype "passive"))
      (node (ref "U1") (pin "21") (pinfunction "PA7_21") (pintype "bidirectional"))
    )
    (net (code "47") (name "/sen_SCLK") (class "Default")
      (node (ref "JP6") (pin "4") (pinfunction "4_4") (pintype "passive"))
      (node (ref "U1") (pin "19") (pinfunction "PA5_19") (pintype "bidirectional"))
    )
    (net (code "48") (name "F_A_3.3") (class "Default")
      (node (ref "C29") (pin "2") (pinfunction "2_2") (pintype "passive"))
      (node (ref "C30") (pin "2") (pinfunction "2_2") (pintype "passive"))
      (node (ref "C31") (pin "2") (pinfunction "2_2") (pintype "passive"))
      (node (ref "C32") (pin "2") (pinfunction "2_2") (pintype "passive"))
      (node (ref "FB3") (pin "2") (pinfunction "2_2") (pintype "passive"))
      (node (ref "U1") (pin "28") (pinfunction "VREF+_28") (pintype "power_in"))
      (node (ref "U1") (pin "29") (pinfunction "VDDA_29") (pintype "power_in"))
    )
    (net (code "49") (name "GND") (class "Default")
      (node (ref "C1") (pin "1") (pinfunction "1_1") (pintype "passive"))
      (node (ref "C10") (pin "1") (pinfunction "1_1") (pintype "passive"))
      (node (ref "C11") (pin "1") (pinfunction "1_1") (pintype "passive"))
      (node (ref "C12") (pin "1") (pinfunction "1_1") (pintype "passive"))
      (node (ref "C2") (pin "1") (pinfunction "1_1") (pintype "passive"))
      (node (ref "C23") (pin "1") (pinfunction "1_1") (pintype "passive"))
      (node (ref "C24") (pin "1") (pinfunction "1_1") (pintype "passive"))
      (node (ref "C25") (pin "1") (pinfunction "1_1") (pintype "passive"))
      (node (ref "C26") (pin "1") (pinfunction "1_1") (pintype "passive"))
      (node (ref "C27") (pin "1") (pinfunction "1_1") (pintype "passive"))
      (node (ref "C28") (pin "1") (pinfunction "1_1") (pintype "passive"))
      (node (ref "C29") (pin "1") (pinfunction "1_1") (pintype "passive"))
      (node (ref "C3") (pin "1") (pinfunction "1_1") (pintype "passive"))
      (node (ref "C30") (pin "1") (pinfunction "1_1") (pintype "passive"))
      (node (ref "C31") (pin "1") (pinfunction "1_1") (pintype "passive"))
      (node (ref "C32") (pin "1") (pinfunction "1_1") (pintype "passive"))
      (node (ref "C33") (pin "1") (pinfunction "1_1") (pintype "passive"))
      (node (ref "C34") (pin "1") (pinfunction "1_1") (pintype "passive"))
      (node (ref "C37") (pin "1") (pinfunction "1_1") (pintype "passive"))
      (node (ref "C38") (pin "1") (pinfunction "1_1") (pintype "passive"))
      (node (ref "C39") (pin "1") (pinfunction "1_1") (pintype "passive"))
      (node (ref "C4") (pin "1") (pinfunction "1_1") (pintype "passive"))
      (node (ref "C41") (pin "1") (pinfunction "1_1") (pintype "passive"))
      (node (ref "C42") (pin "1") (pinfunction "1_1") (pintype "passive"))
      (node (ref "C5") (pin "1") (pinfunction "1_1") (pintype "passive"))
      (node (ref "C52") (pin "1") (pinfunction "1_1") (pintype "passive"))
      (node (ref "C53") (pin "1") (pinfunction "1_1") (pintype "passive"))
      (node (ref "C54") (pin "1") (pinfunction "1_1") (pintype "passive"))
      (node (ref "C55") (pin "1") (pinfunction "1_1") (pintype "passive"))
      (node (ref "C6") (pin "1") (pinfunction "1_1") (pintype "passive"))
      (node (ref "C7") (pin "1") (pinfunction "1_1") (pintype "passive"))
      (node (ref "C8") (pin "1") (pinfunction "1_1") (pintype "passive"))
      (node (ref "JP3") (pin "4") (pinfunction "4_4") (pintype "passive"))
      (node (ref "JP5") (pin "3") (pinfunction "3_3") (pintype "passive"))
      (node (ref "JP6") (pin "2") (pinfunction "2_2") (pintype "passive"))
      (node (ref "LMR51610XDBVR") (pin "2") (pinfunction "GND_2") (pintype "passive"))
      (node (ref "P1") (pin "4") (pinfunction "4_4") (pintype "passive"))
      (node (ref "R27") (pin "1") (pinfunction "1_1") (pintype "passive"))
      (node (ref "R29") (pin "1") (pinfunction "1_1") (pintype "passive"))
      (node (ref "R3") (pin "1") (pinfunction "1_1") (pintype "passive"))
      (node (ref "R30") (pin "1") (pinfunction "1_1") (pintype "passive"))
      (node (ref "R32") (pin "2") (pinfunction "2_2") (pintype "passive"))
      (node (ref "R5") (pin "1") (pinfunction "1_1") (pintype "passive"))
      (node (ref "S1") (pin "2") (pinfunction "2_2") (pintype "passive"))
      (node (ref "S1") (pin "3") (pinfunction "3_3") (pintype "passive"))
      (node (ref "U1") (pin "15") (pinfunction "VSS_15") (pintype "power_in"))
      (node (ref "U1") (pin "27") (pinfunction "VSSA_27") (pintype "power_in"))
      (node (ref "U1") (pin "31") (pinfunction "VSS_31") (pintype "power_in"))
      (node (ref "U1") (pin "47") (pinfunction "VSS_47") (pintype "power_in"))
      (node (ref "U1") (pin "63") (pinfunction "VSS_63") (pintype "power_in"))
      (node (ref "U10") (pin "2") (pinfunction "GND_2") (pintype "passive"))
      (node (ref "U11") (pin "4") (pinfunction "GND_4") (pintype "passive"))
      (node (ref "U11") (pin "7") (pinfunction "REF1_7") (pintype "passive"))
      (node (ref "U12") (pin "4") (pinfunction "GND_4") (pintype "passive"))
      (node (ref "U12") (pin "7") (pinfunction "REF1_7") (pintype "passive"))
      (node (ref "U2") (pin "25") (pinfunction "AGND_25") (pintype "passive"))
      (node (ref "U2") (pin "39") (pinfunction "GND_39") (pintype "passive"))
      (node (ref "U2") (pin "41") (pinfunction "EP_41") (pintype "passive"))
      (node (ref "U3") (pin "2") (pinfunction "GND_2") (pintype "passive"))
      (node (ref "X1") (pin "2") (pinfunction "2_2") (pintype "passive"))
      (node (ref "X1") (pin "4") (pinfunction "4_4") (pintype "passive"))
    )
    (net (code "50") (name "GND_P") (class "Default")
      (node (ref "C13") (pin "1") (pinfunction "1_1") (pintype "passive"))
      (node (ref "C14") (pin "1") (pinfunction "1_1") (pintype "passive"))
      (node (ref "C15") (pin "1") (pinfunction "1_1") (pintype "passive"))
      (node (ref "C16") (pin "1") (pinfunction "1_1") (pintype "passive"))
      (node (ref "C17") (pin "1") (pinfunction "1_1") (pintype "passive"))
      (node (ref "C18") (pin "1") (pinfunction "1_1") (pintype "passive"))
      (node (ref "C19") (pin "1") (pinfunction "1_1") (pintype "passive"))
      (node (ref "C20") (pin "1") (pinfunction "1_1") (pintype "passive"))
      (node (ref "C21") (pin "1") (pinfunction "1_1") (pintype "passive"))
      (node (ref "C22") (pin "1") (pinfunction "1_1") (pintype "passive"))
      (node (ref "C44") (pin "1") (pinfunction "1_1") (pintype "passive"))
      (node (ref "C45") (pin "1") (pinfunction "1_1") (pintype "passive"))
      (node (ref "C46") (pin "1") (pinfunction "1_1") (pintype "passive"))
      (node (ref "C47") (pin "1") (pinfunction "1_1") (pintype "passive"))
      (node (ref "C50") (pin "1") (pinfunction "1_1") (pintype "passive"))
      (node (ref "C51") (pin "1") (pinfunction "1_1") (pintype "passive"))
      (node (ref "D3") (pin "1") (pinfunction "A_1") (pintype "passive"))
      (node (ref "D6") (pin "1") (pinfunction "A_1") (pintype "passive"))
      (node (ref "D9") (pin "1") (pinfunction "A_1") (pintype "passive"))
      (node (ref "JP2") (pin "2") (pinfunction "2_2") (pintype "passive"))
      (node (ref "JP2") (pin "3") (pinfunction "3_3") (pintype "passive"))
      (node (ref "JP2") (pin "4") (pinfunction "4_4") (pintype "passive"))
      (node (ref "R32") (pin "1") (pinfunction "1_1") (pintype "passive"))
      (node (ref "TVS1") (pin "2") (pinfunction "K_2") (pintype "passive"))
      (node (ref "TVS2") (pin "2") (pinfunction "K_2") (pintype "passive"))
      (node (ref "U2") (pin "10") (pinfunction "SNA_10") (pintype "passive"))
      (node (ref "U2") (pin "11") (pinfunction "SNB_11") (pintype "passive"))
      (node (ref "U2") (pin "12") (pinfunction "SPB_12") (pintype "passive"))
      (node (ref "U2") (pin "19") (pinfunction "SPC_19") (pintype "passive"))
      (node (ref "U2") (pin "20") (pinfunction "SNC_20") (pintype "passive"))
      (node (ref "U2") (pin "9") (pinfunction "SPA_9") (pintype "passive"))
      (node (ref "U5") (pin "1") (pinfunction "S_1") (pintype "passive"))
      (node (ref "U5") (pin "2") (pinfunction "S_2") (pintype "passive"))
      (node (ref "U5") (pin "3") (pinfunction "S_3") (pintype "passive"))
      (node (ref "U7") (pin "1") (pinfunction "S_1") (pintype "passive"))
      (node (ref "U7") (pin "2") (pinfunction "S_2") (pintype "passive"))
      (node (ref "U7") (pin "3") (pinfunction "S_3") (pintype "passive"))
      (node (ref "U9") (pin "1") (pinfunction "S_1") (pintype "passive"))
      (node (ref "U9") (pin "2") (pinfunction "S_2") (pintype "passive"))
      (node (ref "U9") (pin "3") (pinfunction "S_3") (pintype "passive"))
    )
    (net (code "51") (name "Net-(C43-Pad2)") (class "Default")
      (node (ref "C43") (pin "2") (pinfunction "2_2") (pintype "passive"))
      (node (ref "R14") (pin "1") (pinfunction "1_1") (pintype "passive"))
    )
    (net (code "52") (name "Net-(C44-Pad2)") (class "Default")
      (node (ref "C44") (pin "2") (pinfunction "2_2") (pintype "passive"))
      (node (ref "R15") (pin "1") (pinfunction "1_1") (pintype "passive"))
    )
    (net (code "53") (name "Net-(C46-Pad2)") (class "Default")
      (node (ref "C46") (pin "2") (pinfunction "2_2") (pintype "passive"))
      (node (ref "R17") (pin "1") (pinfunction "1_1") (pintype "passive"))
    )
    (net (code "54") (name "Net-(C48-Pad2)") (class "Default")
      (node (ref "C48") (pin "2") (pinfunction "2_2") (pintype "passive"))
      (node (ref "R16") (pin "1") (pinfunction "1_1") (pintype "passive"))
    )
    (net (code "55") (name "Net-(C49-Pad2)") (class "Default")
      (node (ref "C49") (pin "2") (pinfunction "2_2") (pintype "passive"))
      (node (ref "R25") (pin "1") (pinfunction "1_1") (pintype "passive"))
    )
    (net (code "56") (name "Net-(C50-Pad2)") (class "Default")
      (node (ref "C50") (pin "2") (pinfunction "2_2") (pintype "passive"))
      (node (ref "R24") (pin "1") (pinfunction "1_1") (pintype "passive"))
    )
    (net (code "57") (name "Net-(C53-Pad2)") (class "Default")
      (node (ref "C53") (pin "2") (pinfunction "2_2") (pintype "passive"))
      (node (ref "R28") (pin "1") (pinfunction "1_1") (pintype "passive"))
      (node (ref "R29") (pin "2") (pinfunction "2_2") (pintype "passive"))
      (node (ref "R33") (pin "2") (pinfunction "2_2") (pintype "passive"))
    )
    (net (code "58") (name "Net-(D1-A)") (class "Default")
      (node (ref "D1") (pin "1") (pinfunction "A_1") (pintype "passive"))
      (node (ref "R11") (pin "1") (pinfunction "1_1") (pintype "passive"))
      (node (ref "U4") (pin "4") (pinfunction "G_4") (pintype "passive"))
    )
    (net (code "59") (name "Net-(D2-A)") (class "Default")
      (node (ref "D2") (pin "1") (pinfunction "A_1") (pintype "passive"))
      (node (ref "D3") (pin "2") (pinfunction "K_2") (pintype "passive"))
      (node (ref "R12") (pin "1") (pinfunction "1_1") (pintype "passive"))
      (node (ref "U5") (pin "4") (pinfunction "G_4") (pintype "passive"))
    )
    (net (code "60") (name "Net-(D4-A)") (class "Default")
      (node (ref "D4") (pin "1") (pinfunction "A_1") (pintype "passive"))
      (node (ref "D6") (pin "2") (pinfunction "K_2") (pintype "passive"))
      (node (ref "R19") (pin "1") (pinfunction "1_1") (pintype "passive"))
      (node (ref "U7") (pin "4") (pinfunction "G_4") (pintype "passive"))
    )
    (net (code "61") (name "Net-(D5-A)") (class "Default")
      (node (ref "D5") (pin "1") (pinfunction "A_1") (pintype "passive"))
      (node (ref "R18") (pin "1") (pinfunction "1_1") (pintype "passive"))
      (node (ref "U6") (pin "4") (pinfunction "G_4") (pintype "passive"))
    )
    (net (code "62") (name "Net-(D7-A)") (class "Default")
      (node (ref "D7") (pin "1") (pinfunction "A_1") (pintype "passive"))
      (node (ref "R21") (pin "1") (pinfunction "1_1") (pintype "passive"))
      (node (ref "U8") (pin "4") (pinfunction "G_4") (pintype "passive"))
    )
    (net (code "63") (name "Net-(D8-A)") (class "Default")
      (node (ref "D8") (pin "1") (pinfunction "A_1") (pintype "passive"))
      (node (ref "D9") (pin "2") (pinfunction "K_2") (pintype "passive"))
      (node (ref "R22") (pin "1") (pinfunction "1_1") (pintype "passive"))
      (node (ref "U9") (pin "4") (pinfunction "G_4") (pintype "passive"))
    )
    (net (code "64") (name "Net-(LED1-A)") (class "Default")
      (node (ref "LED1") (pin "1") (pinfunction "A_1") (pintype "passive"))
      (node (ref "R34") (pin "1") (pinfunction "1_1") (pintype "passive"))
    )
    (net (code "65") (name "Net-(LED2-A)") (class "Default")
      (node (ref "LED2") (pin "1") (pinfunction "A_1") (pintype "passive"))
      (node (ref "R35") (pin "1") (pinfunction "1_1") (pintype "passive"))
    )
    (net (code "66") (name "Net-(LMR51610XDBVR-CB)") (class "Default")
      (node (ref "C9") (pin "2") (pinfunction "2_2") (pintype "passive"))
      (node (ref "LMR51610XDBVR") (pin "1") (pinfunction "CB_1") (pintype "passive"))
    )
    (net (code "67") (name "Net-(LMR51610XDBVR-EN)") (class "Default")
      (node (ref "C3") (pin "2") (pinfunction "2_2") (pintype "passive"))
      (node (ref "C4") (pin "2") (pinfunction "2_2") (pintype "passive"))
      (node (ref "C5") (pin "2") (pinfunction "2_2") (pintype "passive"))
      (node (ref "FB1") (pin "1") (pinfunction "1_1") (pintype "passive"))
      (node (ref "LMR51610XDBVR") (pin "4") (pinfunction "EN_4") (pintype "passive"))
      (node (ref "LMR51610XDBVR") (pin "5") (pinfunction "VIN_5") (pintype "passive"))
    )
    (net (code "68") (name "Net-(LMR51610XDBVR-FB)") (class "Default")
      (node (ref "LMR51610XDBVR") (pin "3") (pinfunction "FB_3") (pintype "passive"))
      (node (ref "R2") (pin "1") (pinfunction "1_1") (pintype "passive"))
      (node (ref "R3") (pin "2") (pinfunction "2_2") (pintype "passive"))
    )
    (net (code "69") (name "Net-(LMR51610XDBVR-SW)") (class "Default")
      (node (ref "C9") (pin "1") (pinfunction "1_1") (pintype "passive"))
      (node (ref "L1") (pin "1") (pinfunction "1_1") (pintype "passive"))
      (node (ref "LMR51610XDBVR") (pin "6") (pinfunction "SW_6") (pintype "passive"))
    )
    (net (code "70") (name "Net-(U2-CPH)") (class "Default")
      (node (ref "C36") (pin "2") (pinfunction "2_2") (pintype "passive"))
      (node (ref "U2") (pin "2") (pinfunction "CPH_2") (pintype "passive"))
    )
    (net (code "71") (name "Net-(U2-CPL)") (class "Default")
      (node (ref "C36") (pin "1") (pinfunction "1_1") (pintype "passive"))
      (node (ref "U2") (pin "1") (pinfunction "CPL_1") (pintype "passive"))
    )
    (net (code "72") (name "Net-(U2-DVDD)") (class "Default")
      (node (ref "C39") (pin "2") (pinfunction "2_2") (pintype "passive"))
      (node (ref "U2") (pin "38") (pinfunction "DVDD_38") (pintype "passive"))
    )
    (net (code "73") (name "Net-(U2-VCP)") (class "Default")
      (node (ref "C35") (pin "1") (pinfunction "1_1") (pintype "passive"))
      (node (ref "U2") (pin "5") (pinfunction "VCP_5") (pintype "passive"))
    )
    (net (code "74") (name "Net-(U2-VGLS)") (class "Default")
      (node (ref "C37") (pin "2") (pinfunction "2_2") (pintype "passive"))
      (node (ref "U2") (pin "40") (pinfunction "VGLS_40") (pintype "passive"))
    )
    (net (code "75") (name "Net-(U3-EN)") (class "Default")
      (node (ref "C11") (pin "2") (pinfunction "2_2") (pintype "passive"))
      (node (ref "FB2") (pin "2") (pinfunction "2_2") (pintype "passive"))
      (node (ref "U3") (pin "1") (pinfunction "VIN_1") (pintype "passive"))
      (node (ref "U3") (pin "3") (pinfunction "EN_3") (pintype "passive"))
    )
    (net (code "76") (name "Net-(U10-S)") (class "Default")
      (node (ref "R30") (pin "2") (pinfunction "2_2") (pintype "passive"))
      (node (ref "U10") (pin "8") (pinfunction "S_8") (pintype "passive"))
    )
    (net (code "77") (name "VIN") (class "Default")
      (node (ref "C13") (pin "2") (pinfunction "2_2") (pintype "passive"))
      (node (ref "C14") (pin "2") (pinfunction "2_2") (pintype "passive"))
      (node (ref "C15") (pin "2") (pinfunction "2_2") (pintype "passive"))
      (node (ref "C16") (pin "2") (pinfunction "2_2") (pintype "passive"))
      (node (ref "C17") (pin "2") (pinfunction "2_2") (pintype "passive"))
      (node (ref "C18") (pin "2") (pinfunction "2_2") (pintype "passive"))
      (node (ref "C19") (pin "2") (pinfunction "2_2") (pintype "passive"))
      (node (ref "C20") (pin "2") (pinfunction "2_2") (pintype "passive"))
      (node (ref "C21") (pin "2") (pinfunction "2_2") (pintype "passive"))
      (node (ref "C22") (pin "2") (pinfunction "2_2") (pintype "passive"))
      (node (ref "C33") (pin "2") (pinfunction "2_2") (pintype "passive"))
      (node (ref "C34") (pin "2") (pinfunction "2_2") (pintype "passive"))
      (node (ref "C35") (pin "2") (pinfunction "2_2") (pintype "passive"))
      (node (ref "C45") (pin "2") (pinfunction "2_2") (pintype "passive"))
      (node (ref "C47") (pin "2") (pinfunction "2_2") (pintype "passive"))
      (node (ref "C51") (pin "2") (pinfunction "2_2") (pintype "passive"))
      (node (ref "C6") (pin "2") (pinfunction "2_2") (pintype "passive"))
      (node (ref "FB1") (pin "2") (pinfunction "2_2") (pintype "passive"))
      (node (ref "JP2") (pin "1") (pinfunction "1_1") (pintype "passive"))
      (node (ref "R14") (pin "2") (pinfunction "2_2") (pintype "passive"))
      (node (ref "R16") (pin "2") (pinfunction "2_2") (pintype "passive"))
      (node (ref "R25") (pin "2") (pinfunction "2_2") (pintype "passive"))
      (node (ref "R28") (pin "2") (pinfunction "2_2") (pintype "passive"))
      (node (ref "TVS1") (pin "1") (pinfunction "A_1") (pintype "passive"))
      (node (ref "TVS2") (pin "1") (pinfunction "A_1") (pintype "passive"))
      (node (ref "U2") (pin "3") (pinfunction "VM_3") (pintype "passive"))
      (node (ref "U2") (pin "4") (pinfunction "VDRAIN_4") (pintype "passive"))
      (node (ref "U4") (pin "5") (pinfunction "D_5") (pintype "passive"))
      (node (ref "U4") (pin "6") (pinfunction "D_6") (pintype "passive"))
      (node (ref "U4") (pin "7") (pinfunction "D_7") (pintype "passive"))
      (node (ref "U4") (pin "8") (pinfunction "D_8") (pintype "passive"))
      (node (ref "U6") (pin "5") (pinfunction "D_5") (pintype "passive"))
      (node (ref "U6") (pin "6") (pinfunction "D_6") (pintype "passive"))
      (node (ref "U6") (pin "7") (pinfunction "D_7") (pintype "passive"))
      (node (ref "U6") (pin "8") (pinfunction "D_8") (pintype "passive"))
      (node (ref "U8") (pin "5") (pinfunction "D_5") (pintype "passive"))
      (node (ref "U8") (pin "6") (pinfunction "D_6") (pintype "passive"))
      (node (ref "U8") (pin "7") (pinfunction "D_7") (pintype "passive"))
      (node (ref "U8") (pin "8") (pinfunction "D_8") (pintype "passive"))
    )
    (net (code "78") (name "unconnected-(U1A-PA2-Pad14)") (class "Default")
      (node (ref "U1") (pin "14") (pinfunction "PA2_14") (pintype "bidirectional+no_connect"))
    )
    (net (code "79") (name "unconnected-(U1A-PA3-Pad17)") (class "Default")
      (node (ref "U1") (pin "17") (pinfunction "PA3_17") (pintype "bidirectional+no_connect"))
    )
    (net (code "80") (name "unconnected-(U1A-PA4-Pad18)") (class "Default")
      (node (ref "U1") (pin "18") (pinfunction "PA4_18") (pintype "bidirectional+no_connect"))
    )
    (net (code "81") (name "unconnected-(U1A-PA6-Pad20)") (class "Default")
      (node (ref "U1") (pin "20") (pinfunction "PA6_20") (pintype "bidirectional+no_connect"))
    )
    (net (code "82") (name "unconnected-(U1A-PA11-Pad45)") (class "Default")
      (node (ref "U1") (pin "45") (pinfunction "PA11_45") (pintype "bidirectional+no_connect"))
    )
    (net (code "83") (name "unconnected-(U1A-PA12-Pad46)") (class "Default")
      (node (ref "U1") (pin "46") (pinfunction "PA12_46") (pintype "bidirectional+no_connect"))
    )
    (net (code "84") (name "unconnected-(U1A-PA15-Pad51)") (class "Default")
      (node (ref "U1") (pin "51") (pinfunction "PA15_51") (pintype "bidirectional+no_connect"))
    )
    (net (code "85") (name "unconnected-(U1A-PB1-Pad25)") (class "Default")
      (node (ref "U1") (pin "25") (pinfunction "PB1_25") (pintype "bidirectional+no_connect"))
    )
    (net (code "86") (name "unconnected-(U1A-PB3-Pad56)") (class "Default")
      (node (ref "U1") (pin "56") (pinfunction "PB3_56") (pintype "bidirectional+no_connect"))
    )
    (net (code "87") (name "unconnected-(U1A-PB7-Pad60)") (class "Default")
      (node (ref "U1") (pin "60") (pinfunction "PB7_60") (pintype "bidirectional+no_connect"))
    )
    (net (code "88") (name "unconnected-(U1A-PB9-Pad62)") (class "Default")
      (node (ref "U1") (pin "62") (pinfunction "PB9_62") (pintype "bidirectional+no_connect"))
    )
    (net (code "89") (name "unconnected-(U1A-PB10-Pad30)") (class "Default")
      (node (ref "U1") (pin "30") (pinfunction "PB10_30") (pintype "bidirectional+no_connect"))
    )
    (net (code "90") (name "unconnected-(U1A-PB11-Pad33)") (class "Default")
      (node (ref "U1") (pin "33") (pinfunction "PB11_33") (pintype "bidirectional+no_connect"))
    )
    (net (code "91") (name "unconnected-(U1A-PB12-Pad34)") (class "Default")
      (node (ref "U1") (pin "34") (pinfunction "PB12_34") (pintype "bidirectional+no_connect"))
    )
    (net (code "92") (name "unconnected-(U1A-PB15-Pad37)") (class "Default")
      (node (ref "U1") (pin "37") (pinfunction "PB15_37") (pintype "bidirectional+no_connect"))
    )
    (net (code "93") (name "unconnected-(U1A-PC2-Pad10)") (class "Default")
      (node (ref "U1") (pin "10") (pinfunction "PC2_10") (pintype "bidirectional+no_connect"))
    )
    (net (code "94") (name "unconnected-(U1A-PC3-Pad11)") (class "Default")
      (node (ref "U1") (pin "11") (pinfunction "PC3_11") (pintype "bidirectional+no_connect"))
    )
    (net (code "95") (name "unconnected-(U1A-PC6-Pad38)") (class "Default")
      (node (ref "U1") (pin "38") (pinfunction "PC6_38") (pintype "bidirectional+no_connect"))
    )
    (net (code "96") (name "unconnected-(U1A-PC7-Pad39)") (class "Default")
      (node (ref "U1") (pin "39") (pinfunction "PC7_39") (pintype "bidirectional+no_connect"))
    )
    (net (code "97") (name "unconnected-(U1A-PC8-Pad40)") (class "Default")
      (node (ref "U1") (pin "40") (pinfunction "PC8_40") (pintype "bidirectional+no_connect"))
    )
    (net (code "98") (name "unconnected-(U1A-PC9-Pad41)") (class "Default")
      (node (ref "U1") (pin "41") (pinfunction "PC9_41") (pintype "bidirectional+no_connect"))
    )
    (net (code "99") (name "unconnected-(U1A-PC13-Pad2)") (class "Default")
      (node (ref "U1") (pin "2") (pinfunction "PC13_2") (pintype "bidirectional+no_connect"))
    )
    (net (code "100") (name "unconnected-(U1A-PD2-Pad55)") (class "Default")
      (node (ref "U1") (pin "55") (pinfunction "PD2_55") (pintype "bidirectional+no_connect"))
    )
    (net (code "101") (name "unconnected-(U2-SOA-Pad23)") (class "Default")
      (node (ref "U2") (pin "23") (pinfunction "SOA_23") (pintype "passive+no_connect"))
    )
    (net (code "102") (name "unconnected-(U2-SOB-Pad22)") (class "Default")
      (node (ref "U2") (pin "22") (pinfunction "SOB_22") (pintype "passive+no_connect"))
    )
    (net (code "103") (name "unconnected-(U2-SOC-Pad21)") (class "Default")
      (node (ref "U2") (pin "21") (pinfunction "SOC_21") (pintype "passive+no_connect"))
    )
    (net (code "104") (name "unconnected-(U3-NC-Pad4)") (class "Default")
      (node (ref "U3") (pin "4") (pinfunction "NC_4") (pintype "passive"))
    )
    (net (code "105") (name "unconnected-(U11-NC-Pad1)") (class "Default")
      (node (ref "U11") (pin "1") (pinfunction "NC_1") (pintype "passive"))
    )
    (net (code "106") (name "unconnected-(U12-NC-Pad1)") (class "Default")
      (node (ref "U12") (pin "1") (pinfunction "NC_1") (pintype "passive"))
    )
  )
)
